# regulated_sensorTH_thesis.net
KiCad netlist of a schematic drawn in EAGLE
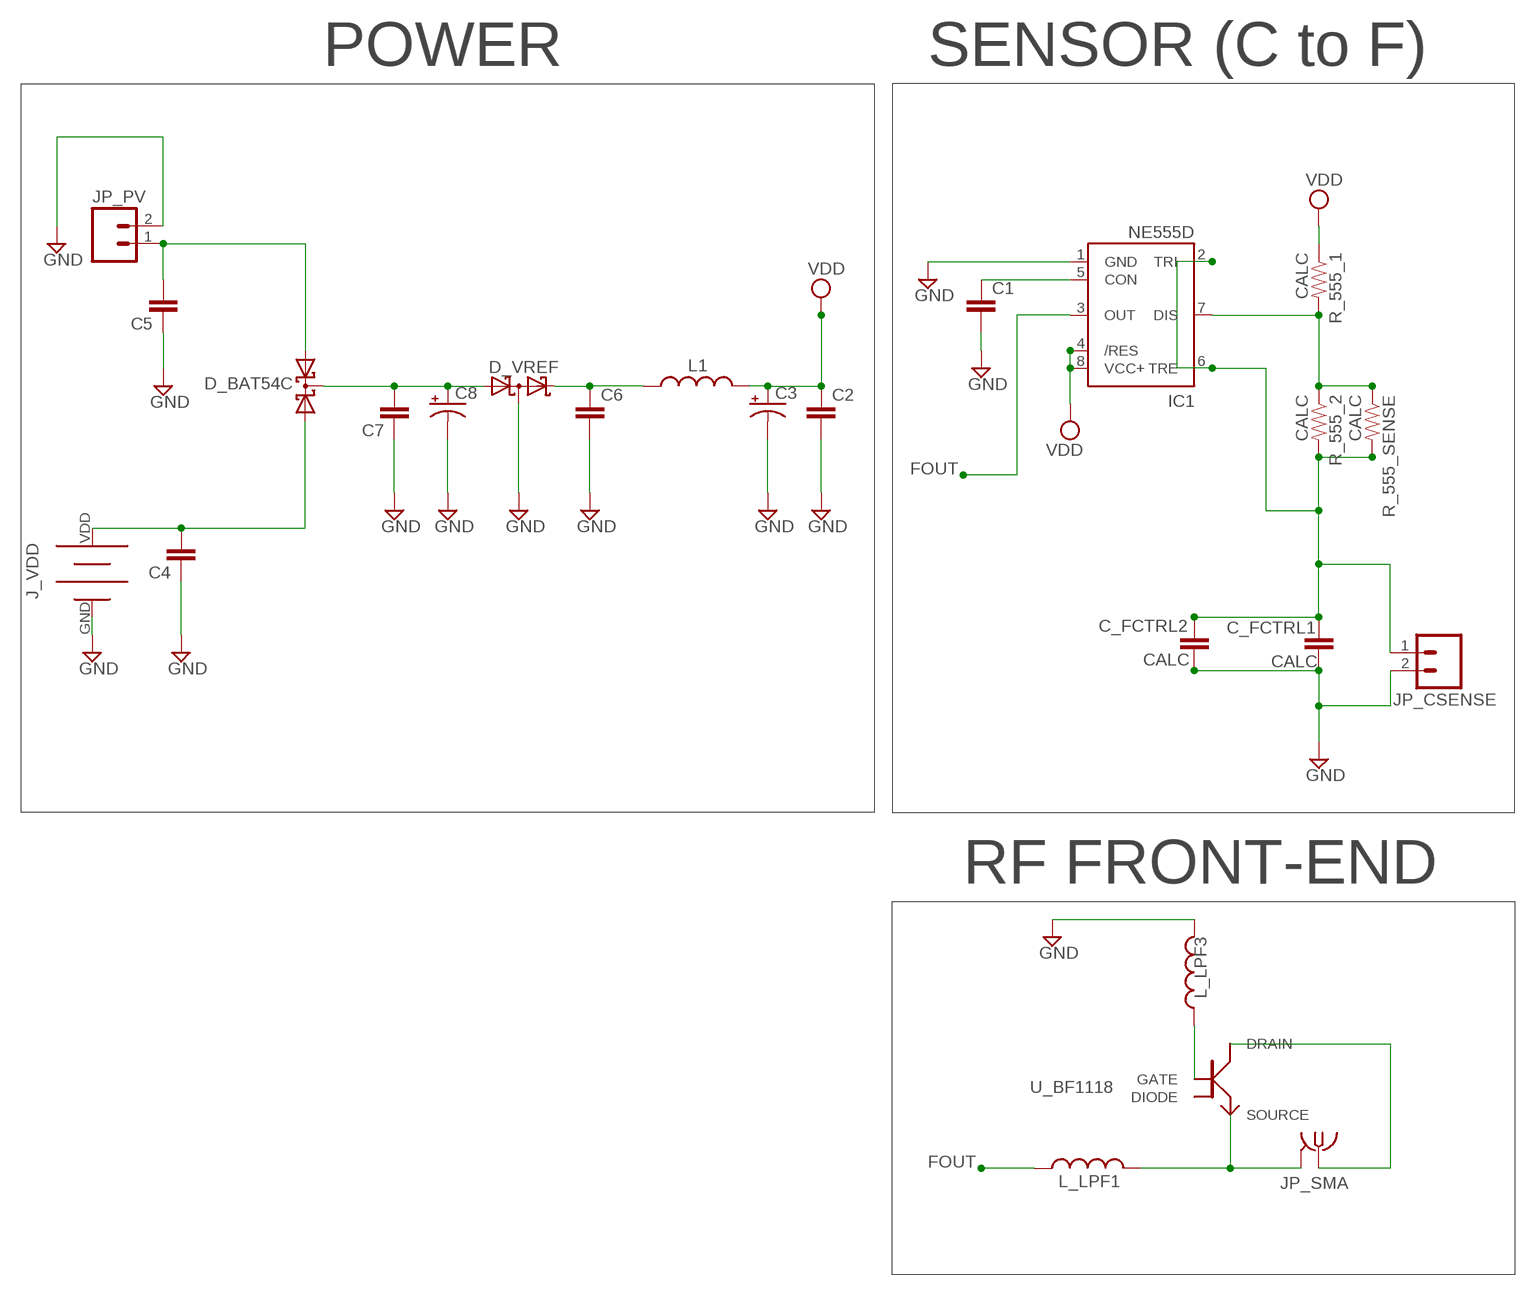
[diagram p0: schematic, sheet 1]

(export (version "E")
  (design (tool "Eeschema 10.0.6"))
  (components
    (comp (ref "C1")
      (value "CAP0603-CAP")
      (footprint "eagle-import:0603-CAP")
      (libsource (lib "eagle-import") (part "CAP0603-CAP"))
    )
    (comp (ref "C2")
      (value "CAP0603-CAP")
      (footprint "eagle-import:0603-CAP")
      (libsource (lib "eagle-import") (part "CAP0603-CAP"))
    )
    (comp (ref "C3")
      (value "CAP_POL1206")
      (footprint "eagle-import:EIA3216")
      (libsource (lib "eagle-import") (part "CAP_POL1206"))
    )
    (comp (ref "C4")
      (value "CAP0603-CAP")
      (footprint "eagle-import:0603-CAP")
      (libsource (lib "eagle-import") (part "CAP0603-CAP"))
    )
    (comp (ref "C5")
      (value "CAP0603-CAP")
      (footprint "eagle-import:0603-CAP")
      (libsource (lib "eagle-import") (part "CAP0603-CAP"))
    )
    (comp (ref "C6")
      (value "CAP0603-CAP")
      (footprint "eagle-import:0603-CAP")
      (libsource (lib "eagle-import") (part "CAP0603-CAP"))
    )
    (comp (ref "C7")
      (value "CAP0603-CAP")
      (footprint "eagle-import:0603-CAP")
      (libsource (lib "eagle-import") (part "CAP0603-CAP"))
    )
    (comp (ref "C8")
      (value "CAP_POL1206")
      (footprint "eagle-import:EIA3216")
      (libsource (lib "eagle-import") (part "CAP_POL1206"))
    )
    (comp (ref "C_FCTRL1")
      (value "CALC")
      (footprint "eagle-import:0603-CAP")
      (libsource (lib "eagle-import") (part "CAP0603-CAP"))
    )
    (comp (ref "C_FCTRL2")
      (value "CALC")
      (footprint "eagle-import:0603-CAP")
      (libsource (lib "eagle-import") (part "CAP0603-CAP"))
    )
    (comp (ref "D_BAT54C")
      (value "BAT54C")
      (footprint "eagle-import:SOT23")
      (libsource (lib "eagle-import") (part "BAT54C"))
    )
    (comp (ref "D_VREF")
      (value "BAT54S")
      (footprint "eagle-import:SOT23")
      (libsource (lib "eagle-import") (part "BAT54S"))
    )
    (comp (ref "IC1")
      (value "NE555D")
      (footprint "eagle-import:SO08")
      (libsource (lib "eagle-import") (part "NE555D"))
    )
    (comp (ref "JP_CSENSE")
      (value "M02LOCK")
      (footprint "eagle-import:1X02_LOCK")
      (libsource (lib "eagle-import") (part "M02LOCK"))
    )
    (comp (ref "JP_PV")
      (value "M02LOCK")
      (footprint "eagle-import:1X02_LOCK")
      (libsource (lib "eagle-import") (part "M02LOCK"))
    )
    (comp (ref "JP_SMA")
      (value "SMA-142-0701-881/886")
      (footprint "eagle-import:J502-ND-142-0701-881_886")
      (fields (field (name "MF") "JOHNSON COMPONENTS") (field (name "MPN") "142-0701-881"))
      (libsource (lib "eagle-import") (part "SMA-142-0701-881/886"))
    )
    (comp (ref "L1")
      (value "INDUCTOR0603")
      (footprint "eagle-import:0603")
      (libsource (lib "eagle-import") (part "INDUCTOR0603"))
    )
    (comp (ref "L_LPF1")
      (value "INDUCTOR0603")
      (footprint "eagle-import:0603")
      (libsource (lib "eagle-import") (part "INDUCTOR0603"))
    )
    (comp (ref "L_LPF3")
      (value "INDUCTOR0603")
      (footprint "eagle-import:0603")
      (libsource (lib "eagle-import") (part "INDUCTOR0603"))
    )
    (comp (ref "R_555_1")
      (value "CALC")
      (footprint "eagle-import:0805")
      (libsource (lib "eagle-import") (part "RESISTOR0805-RES"))
    )
    (comp (ref "R_555_2")
      (value "CALC")
      (footprint "eagle-import:0603-RES")
      (libsource (lib "eagle-import") (part "RESISTOR0603-RES"))
    )
    (comp (ref "R_555_SENSE")
      (value "CALC")
      (footprint "eagle-import:0603-RES")
      (libsource (lib "eagle-import") (part "RESISTOR0603-RES"))
    )
    (comp (ref "U$1")
      (value "BATTERY_AAA_EAGLE_PLASTIC_DEVICES_DOUBLE")
      (footprint "eagle-import:BATTERY-AAA-50MM-DOUBLE")
      (libsource (lib "eagle-import") (part "BATTERY_AAA_EAGLE_PLASTIC_DEVICES_DOUBLE"))
    )
    (comp (ref "U_BF1118")
      (value "BF1118SOT343R_NXP")
      (footprint "eagle-import:SOT343R")
      (libsource (lib "eagle-import") (part "BF1118SOT343R_NXP"))
    )
  )
  (nets
    (net (code "1") (name "/FOUT") (class "Default")
      (node (ref "IC1") (pin "3") (pinfunction "OUT_3") (pintype "output"))
      (node (ref "L_LPF1") (pin "1") (pinfunction "1_1") (pintype "passive"))
    )
    (net (code "2") (name "GND") (class "Default")
      (node (ref "C1") (pin "2") (pinfunction "2_2") (pintype "passive"))
      (node (ref "C2") (pin "2") (pinfunction "2_2") (pintype "passive"))
      (node (ref "C3") (pin "C") (pinfunction "-_C") (pintype "passive"))
      (node (ref "C4") (pin "1") (pinfunction "1_1") (pintype "passive"))
      (node (ref "C5") (pin "1") (pinfunction "1_1") (pintype "passive"))
      (node (ref "C6") (pin "2") (pinfunction "2_2") (pintype "passive"))
      (node (ref "C7") (pin "1") (pinfunction "1_1") (pintype "passive"))
      (node (ref "C8") (pin "C") (pinfunction "-_C") (pintype "passive"))
      (node (ref "C_FCTRL1") (pin "2") (pinfunction "2_2") (pintype "passive"))
      (node (ref "C_FCTRL2") (pin "2") (pinfunction "2_2") (pintype "passive"))
      (node (ref "D_VREF") (pin "3") (pinfunction "C1A2_3") (pintype "passive"))
      (node (ref "IC1") (pin "1") (pinfunction "GND_1") (pintype "power_in"))
      (node (ref "JP_CSENSE") (pin "2") (pinfunction "2_2") (pintype "passive"))
      (node (ref "JP_PV") (pin "2") (pinfunction "2_2") (pintype "passive"))
      (node (ref "L_LPF3") (pin "2") (pinfunction "2_2") (pintype "passive"))
      (node (ref "U$1") (pin "GND") (pinfunction "GND_GND") (pintype "bidirectional"))
    )
    (net (code "3") (name "Net-(C8-+)") (class "Default")
      (node (ref "C7") (pin "2") (pinfunction "2_2") (pintype "passive"))
      (node (ref "C8") (pin "A") (pinfunction "+_A") (pintype "passive"))
      (node (ref "D_BAT54C") (pin "3") (pinfunction "CC_3") (pintype "passive"))
      (node (ref "D_VREF") (pin "1") (pinfunction "A1_1") (pintype "passive"))
    )
    (net (code "4") (name "Net-(D_BAT54C-A1)") (class "Default")
      (node (ref "C5") (pin "2") (pinfunction "2_2") (pintype "passive"))
      (node (ref "D_BAT54C") (pin "1") (pinfunction "A1_1") (pintype "passive"))
      (node (ref "JP_PV") (pin "1") (pinfunction "1_1") (pintype "passive"))
    )
    (net (code "5") (name "Net-(D_BAT54C-A2)") (class "Default")
      (node (ref "C4") (pin "2") (pinfunction "2_2") (pintype "passive"))
      (node (ref "D_BAT54C") (pin "2") (pinfunction "A2_2") (pintype "passive"))
      (node (ref "U$1") (pin "VDD") (pinfunction "VDD_VDD") (pintype "bidirectional"))
    )
    (net (code "6") (name "Net-(D_VREF-C2)") (class "Default")
      (node (ref "C6") (pin "1") (pinfunction "1_1") (pintype "passive"))
      (node (ref "D_VREF") (pin "2") (pinfunction "C2_2") (pintype "passive"))
      (node (ref "L1") (pin "1") (pinfunction "1_1") (pintype "passive"))
    )
    (net (code "7") (name "Net-(IC1-CON)") (class "Default")
      (node (ref "C1") (pin "1") (pinfunction "1_1") (pintype "passive"))
      (node (ref "IC1") (pin "5") (pinfunction "CON_5") (pintype "input"))
    )
    (net (code "8") (name "Net-(IC1-DIS)") (class "Default")
      (node (ref "IC1") (pin "7") (pinfunction "DIS_7") (pintype "input"))
      (node (ref "R_555_1") (pin "2") (pinfunction "2_2") (pintype "passive"))
      (node (ref "R_555_2") (pin "1") (pinfunction "1_1") (pintype "passive"))
      (node (ref "R_555_SENSE") (pin "1") (pinfunction "1_1") (pintype "passive"))
    )
    (net (code "9") (name "Net-(IC1-TRE)") (class "Default")
      (node (ref "C_FCTRL1") (pin "1") (pinfunction "1_1") (pintype "passive"))
      (node (ref "C_FCTRL2") (pin "1") (pinfunction "1_1") (pintype "passive"))
      (node (ref "IC1") (pin "2") (pinfunction "TRI_2") (pintype "input"))
      (node (ref "IC1") (pin "6") (pinfunction "TRE_6") (pintype "input"))
      (node (ref "JP_CSENSE") (pin "1") (pinfunction "1_1") (pintype "passive"))
      (node (ref "R_555_2") (pin "2") (pinfunction "2_2") (pintype "passive"))
      (node (ref "R_555_SENSE") (pin "2") (pinfunction "2_2") (pintype "passive"))
    )
    (net (code "10") (name "Net-(U_BF1118-DRAIN)") (class "Default")
      (node (ref "JP_SMA") (pin "1") (pinfunction "1_1") (pintype "passive"))
      (node (ref "U_BF1118") (pin "4") (pinfunction "DRAIN_4") (pintype "bidirectional"))
    )
    (net (code "11") (name "Net-(U_BF1118-GATE)") (class "Default")
      (node (ref "L_LPF3") (pin "1") (pinfunction "1_1") (pintype "passive"))
      (node (ref "U_BF1118") (pin "1") (pinfunction "GATE_1") (pintype "bidirectional"))
    )
    (net (code "12") (name "Net-(U_BF1118-SOURCE)") (class "Default")
      (node (ref "JP_SMA") (pin "G@1") (pinfunction "2_G@1") (pintype "passive"))
      (node (ref "JP_SMA") (pin "G@2") (pinfunction "2_G@2") (pintype "passive"))
      (node (ref "JP_SMA") (pin "G@3") (pinfunction "2_G@3") (pintype "passive"))
      (node (ref "JP_SMA") (pin "G@4") (pinfunction "2_G@4") (pintype "passive"))
      (node (ref "L_LPF1") (pin "2") (pinfunction "2_2") (pintype "passive"))
      (node (ref "U_BF1118") (pin "3") (pinfunction "SOURCE_3") (pintype "bidirectional"))
    )
    (net (code "13") (name "VDD") (class "Default")
      (node (ref "C2") (pin "1") (pinfunction "1_1") (pintype "passive"))
      (node (ref "C3") (pin "A") (pinfunction "+_A") (pintype "passive"))
      (node (ref "IC1") (pin "4") (pinfunction "/RES_4") (pintype "input"))
      (node (ref "IC1") (pin "8") (pinfunction "VCC+_8") (pintype "power_in"))
      (node (ref "L1") (pin "2") (pinfunction "2_2") (pintype "passive"))
      (node (ref "R_555_1") (pin "1") (pinfunction "1_1") (pintype "passive"))
    )
    (net (code "14") (name "unconnected-(U_BF1118-DIODE-Pad2)") (class "Default")
      (node (ref "U_BF1118") (pin "2") (pinfunction "DIODE_2") (pintype "bidirectional"))
    )
  )
)
